# Step-to-TalkV2.net
KiCad netlist of a schematic drawn in EAGLE
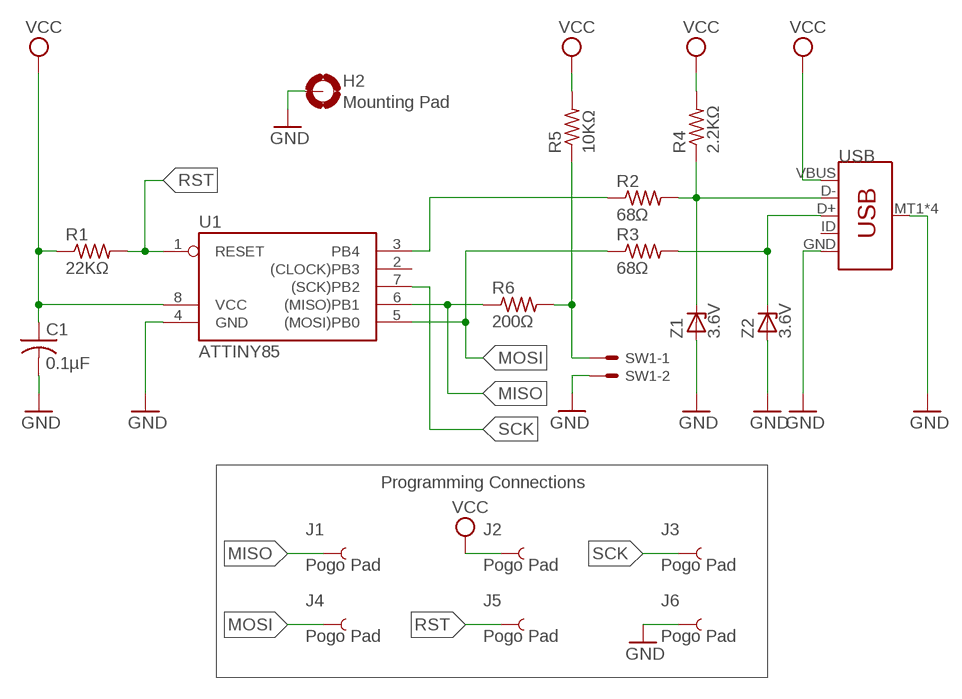
[diagram p0: schematic, sheet 1]

(export (version "E")
  (design (tool "Eeschema 10.0.6"))
  (components
    (comp (ref "C1")
      (value "0.1µF")
      (footprint "eagle-import:C0603")
      (libsource (lib "eagle-import") (part "C-USC0603"))
    )
    (comp (ref "H2")
      (value "Mounting Pad")
      (footprint "eagle-import:4,3-PAD")
      (libsource (lib "eagle-import") (part "MOUNT-PAD-ROUND4.3"))
    )
    (comp (ref "J1")
      (value "Pogo Pad")
      (footprint "eagle-import:PAD.03X.03")
      (libsource (lib "eagle-import") (part "TEST-POINT3"))
    )
    (comp (ref "J2")
      (value "Pogo Pad")
      (footprint "eagle-import:PAD.03X.03")
      (libsource (lib "eagle-import") (part "TEST-POINT3"))
    )
    (comp (ref "J3")
      (value "Pogo Pad")
      (footprint "eagle-import:PAD.03X.03")
      (libsource (lib "eagle-import") (part "TEST-POINT3"))
    )
    (comp (ref "J4")
      (value "Pogo Pad")
      (footprint "eagle-import:PAD.03X.03")
      (libsource (lib "eagle-import") (part "TEST-POINT3"))
    )
    (comp (ref "J5")
      (value "Pogo Pad")
      (footprint "eagle-import:PAD.03X.03")
      (libsource (lib "eagle-import") (part "TEST-POINT3"))
    )
    (comp (ref "J6")
      (value "Pogo Pad")
      (footprint "eagle-import:PAD.03X.03")
      (libsource (lib "eagle-import") (part "TEST-POINT3"))
    )
    (comp (ref "R1")
      (value "22KΩ")
      (footprint "eagle-import:R0603")
      (libsource (lib "eagle-import") (part "R-US_R0603"))
    )
    (comp (ref "R2")
      (value "68Ω")
      (footprint "eagle-import:R0603")
      (libsource (lib "eagle-import") (part "R-US_R0603"))
    )
    (comp (ref "R3")
      (value "68Ω")
      (footprint "eagle-import:R0603")
      (libsource (lib "eagle-import") (part "R-US_R0603"))
    )
    (comp (ref "R4")
      (value "2.2KΩ")
      (footprint "eagle-import:R0603")
      (libsource (lib "eagle-import") (part "R-US_R0603"))
    )
    (comp (ref "R5")
      (value "10KΩ")
      (footprint "eagle-import:R0603")
      (libsource (lib "eagle-import") (part "R-US_R0603"))
    )
    (comp (ref "R6")
      (value "200Ω")
      (footprint "eagle-import:R0603")
      (libsource (lib "eagle-import") (part "R-US_R0603"))
    )
    (comp (ref "SW1")
      (value "87438-02")
      (footprint "eagle-import:87438-02")
      (libsource (lib "eagle-import") (part "87438-02"))
    )
    (comp (ref "U1")
      (value "ATTINY85")
      (footprint "eagle-import:SOIC8")
      (libsource (lib "eagle-import") (part "TINY22S"))
    )
    (comp (ref "USB")
      (value "USB_MICRO-B_SMT")
      (footprint "eagle-import:USB-MICROB")
      (libsource (lib "eagle-import") (part "USB_MICRO-B_SMT"))
    )
    (comp (ref "Z1")
      (value "3.6V")
      (footprint "eagle-import:SOD523")
      (libsource (lib "eagle-import") (part "PESD5V0X1UB"))
    )
    (comp (ref "Z2")
      (value "3.6V")
      (footprint "eagle-import:SOD523")
      (libsource (lib "eagle-import") (part "PESD5V0X1UB"))
    )
  )
  (nets
    (net (code "1") (name "GND") (class "Default")
      (node (ref "C1") (pin "2") (pinfunction "2_2") (pintype "passive"))
      (node (ref "H2") (pin "B4,3") (pinfunction "MOUNT_B4,3") (pintype "passive"))
      (node (ref "J6") (pin "P$1") (pinfunction "1_P$1") (pintype "bidirectional"))
      (node (ref "SW1") (pin "2") (pinfunction "S_2") (pintype "passive"))
      (node (ref "U1") (pin "4") (pinfunction "GND_4") (pintype "power_in"))
      (node (ref "USB") (pin "GND") (pinfunction "GND_GND") (pintype "power_in"))
      (node (ref "USB") (pin "MT1") (pinfunction "SHIELD_MT1") (pintype "bidirectional"))
      (node (ref "USB") (pin "MT2") (pinfunction "SHIELD_MT2") (pintype "bidirectional"))
      (node (ref "USB") (pin "P$1") (pinfunction "SHIELD_P$1") (pintype "bidirectional"))
      (node (ref "USB") (pin "P$2") (pinfunction "SHIELD_P$2") (pintype "bidirectional"))
      (node (ref "Z1") (pin "2") (pinfunction "A_2") (pintype "passive"))
      (node (ref "Z2") (pin "2") (pinfunction "A_2") (pintype "passive"))
    )
    (net (code "2") (name "MISO") (class "Default")
      (node (ref "J1") (pin "P$1") (pinfunction "1_P$1") (pintype "bidirectional"))
      (node (ref "R6") (pin "1") (pinfunction "1_1") (pintype "passive"))
      (node (ref "U1") (pin "6") (pinfunction "(MISO)PB1_6") (pintype "bidirectional"))
    )
    (net (code "3") (name "MOSI") (class "Default")
      (node (ref "J4") (pin "P$1") (pinfunction "1_P$1") (pintype "bidirectional"))
      (node (ref "R3") (pin "1") (pinfunction "1_1") (pintype "passive"))
      (node (ref "U1") (pin "5") (pinfunction "(MOSI)PB0_5") (pintype "bidirectional"))
    )
    (net (code "4") (name "Net-(SW1A-S)") (class "Default")
      (node (ref "R5") (pin "1") (pinfunction "1_1") (pintype "passive"))
      (node (ref "R6") (pin "2") (pinfunction "2_2") (pintype "passive"))
      (node (ref "SW1") (pin "1") (pinfunction "S_1") (pintype "passive"))
    )
    (net (code "5") (name "Net-(U1-PB4)") (class "Default")
      (node (ref "R2") (pin "1") (pinfunction "1_1") (pintype "passive"))
      (node (ref "U1") (pin "3") (pinfunction "PB4_3") (pintype "bidirectional"))
    )
    (net (code "6") (name "Net-(Z1-K)") (class "Default")
      (node (ref "R2") (pin "2") (pinfunction "2_2") (pintype "passive"))
      (node (ref "R4") (pin "1") (pinfunction "1_1") (pintype "passive"))
      (node (ref "USB") (pin "D-") (pinfunction "D-_D-") (pintype "bidirectional"))
      (node (ref "Z1") (pin "1") (pinfunction "K_1") (pintype "passive"))
    )
    (net (code "7") (name "Net-(Z2-K)") (class "Default")
      (node (ref "R3") (pin "2") (pinfunction "2_2") (pintype "passive"))
      (node (ref "USB") (pin "D+") (pinfunction "D+_D+") (pintype "bidirectional"))
      (node (ref "Z2") (pin "1") (pinfunction "K_1") (pintype "passive"))
    )
    (net (code "8") (name "RST") (class "Default")
      (node (ref "J5") (pin "P$1") (pinfunction "1_P$1") (pintype "bidirectional"))
      (node (ref "R1") (pin "2") (pinfunction "2_2") (pintype "passive"))
      (node (ref "U1") (pin "1") (pinfunction "RESET_1") (pintype "input"))
    )
    (net (code "9") (name "SCK") (class "Default")
      (node (ref "J3") (pin "P$1") (pinfunction "1_P$1") (pintype "bidirectional"))
      (node (ref "U1") (pin "7") (pinfunction "(SCK)PB2_7") (pintype "bidirectional"))
    )
    (net (code "10") (name "VCC") (class "Default")
      (node (ref "C1") (pin "1") (pinfunction "1_1") (pintype "passive"))
      (node (ref "J2") (pin "P$1") (pinfunction "1_P$1") (pintype "bidirectional"))
      (node (ref "R1") (pin "1") (pinfunction "1_1") (pintype "passive"))
      (node (ref "R4") (pin "2") (pinfunction "2_2") (pintype "passive"))
      (node (ref "R5") (pin "2") (pinfunction "2_2") (pintype "passive"))
      (node (ref "U1") (pin "8") (pinfunction "VCC_8") (pintype "power_in"))
      (node (ref "USB") (pin "VBUS") (pinfunction "VBUS_VBUS") (pintype "power_in"))
    )
    (net (code "11") (name "unconnected-(U1-(CLOCK)PB3-Pad2)") (class "Default")
      (node (ref "U1") (pin "2") (pinfunction "(CLOCK)PB3_2") (pintype "bidirectional"))
    )
    (net (code "12") (name "unconnected-(USB-PadID)") (class "Default")
      (node (ref "USB") (pin "ID") (pinfunction "ID_ID") (pintype "bidirectional"))
    )
  )
)
